# SC-1000527_SCH_IMUPlusMAGIslands_Page1.net
KiCad netlist of a schematic drawn in Altium Designer
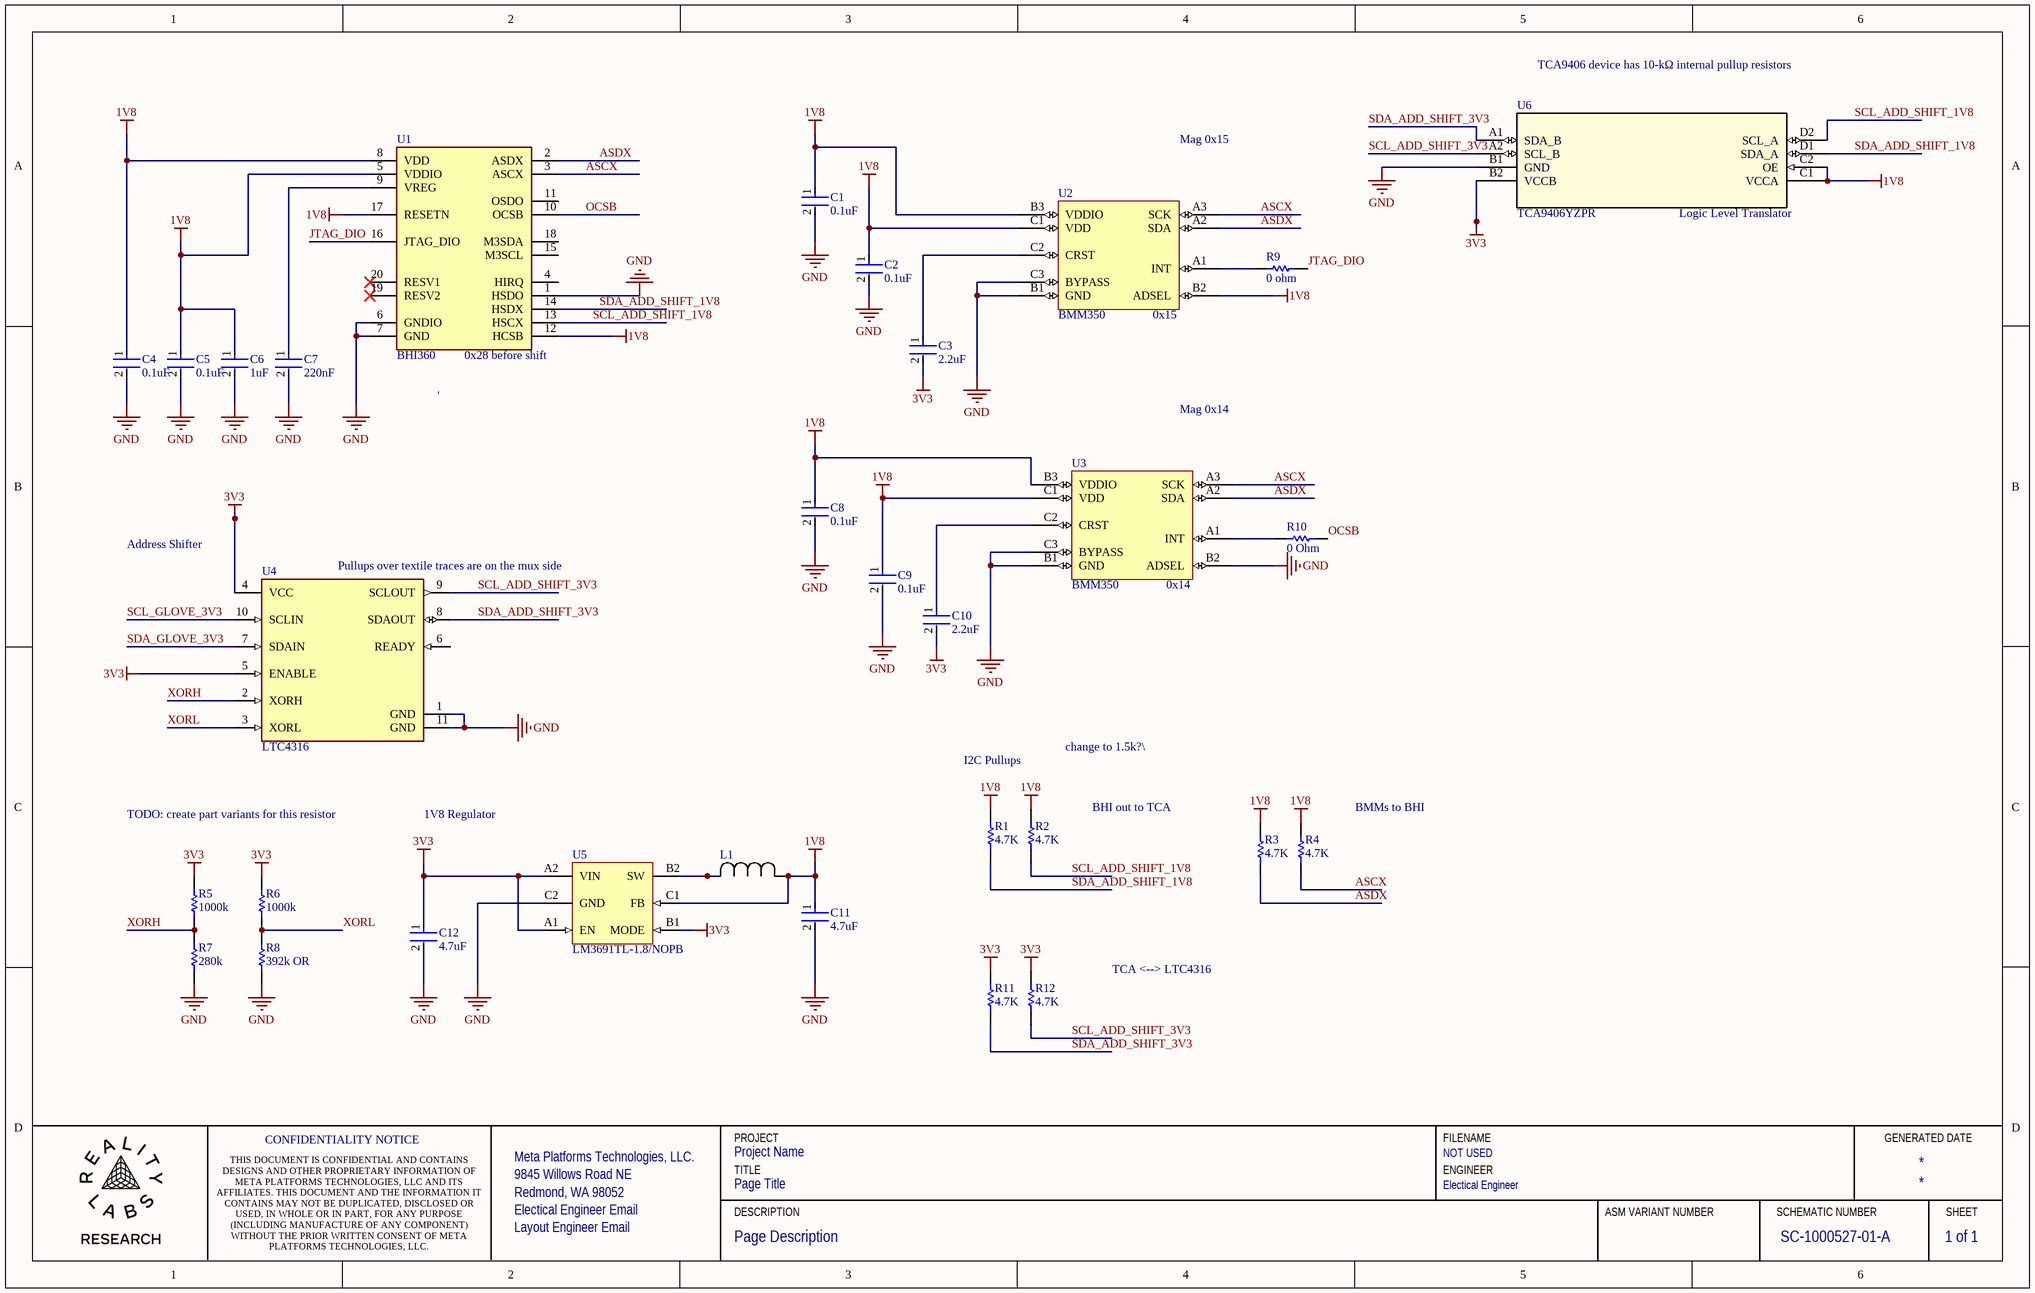
[diagram p0: SC-1000527_SCH_IMUPlusMAGIslands_Page1.SchDoc]

(export (version "E")
  (design (tool "Eeschema 10.0.6"))
  (components
    (comp (ref "C1")
      (value "0.1uF")
      (footprint "FP-GRM033-0_03-IPC_C")
      (description "Chip Multilayer Ceramic Capacitors for General Purpose, 0201, 0.10uF, X5R, 15%, 10%, 10V")
      (fields (field (name "TOLERANCE") "10%") (field (name "VOLTAGE") "10V"))
      (libsource (lib "Altium Content Vault") (part "b4654b650e69147ec39a6b967a45e02"))
    )
    (comp (ref "C2")
      (value "0.1uF")
      (footprint "FP-GRM033-0_03-IPC_C")
      (description "Chip Multilayer Ceramic Capacitors for General Purpose, 0201, 0.10uF, X5R, 15%, 10%, 10V")
      (fields (field (name "TOLERANCE") "10%") (field (name "VOLTAGE") "10V"))
      (libsource (lib "Altium Content Vault") (part "b4654b650e69147ec39a6b967a45e02"))
    )
    (comp (ref "C3")
      (value "2.2uF")
      (footprint "FP-GRM033-0_09-IPC_B")
      (description "Chip Multilayer Ceramic Capacitors for General Purpose, 0201, 2.2uF, X5R, 15%, 10%, 10V")
      (fields (field (name "TOLERANCE") "10%"))
      (libsource (lib "Altium Content Vault") (part "02cd4be3c70576c341d710602a673aa"))
    )
    (comp (ref "C4")
      (value "0.1uF")
      (footprint "FP-GRM033-0_03-IPC_C")
      (description "Chip Multilayer Ceramic Capacitors for General Purpose, 0201, 0.10uF, X5R, 15%, 10%, 10V")
      (fields (field (name "TOLERANCE") "10%") (field (name "VOLTAGE") "10V"))
      (libsource (lib "Altium Content Vault") (part "b4654b650e69147ec39a6b967a45e02"))
    )
    (comp (ref "C5")
      (value "0.1uF")
      (footprint "FP-GRM033-0_03-IPC_C")
      (description "Chip Multilayer Ceramic Capacitors for General Purpose, 0201, 0.10uF, X5R, 15%, 10%, 10V")
      (fields (field (name "TOLERANCE") "10%") (field (name "VOLTAGE") "10V"))
      (libsource (lib "Altium Content Vault") (part "b4654b650e69147ec39a6b967a45e02"))
    )
    (comp (ref "C6")
      (value "1uF")
      (footprint "FP-GRM033-0_05-e01_0_2-IPC_C")
      (description "Chip Multilayer Ceramic Capacitors for General Purpose, 0201, 1.0uF, X5R, 15%, 20%, 4V")
      (fields (field (name "TOLERANCE") "20%"))
      (libsource (lib "Altium Content Vault") (part "02cd4be3c70576c341d710602a673aa"))
    )
    (comp (ref "C7")
      (value "220nF")
      (footprint "FP-GRM033-0_03-MFG")
      (description "Chip Multilayer Ceramic Capacitors for General Purpose, 0201, 0.22uF, X6S, 22%, 10%, 6.3V")
      (fields (field (name "TOLERANCE") "10%"))
      (libsource (lib "Altium Content Vault") (part "b4654b650e69147ec39a6b967a45e02"))
    )
    (comp (ref "C8")
      (value "0.1uF")
      (footprint "FP-GRM033-0_03-IPC_C")
      (description "Chip Multilayer Ceramic Capacitors for General Purpose, 0201, 0.10uF, X5R, 15%, 10%, 10V")
      (fields (field (name "TOLERANCE") "10%") (field (name "VOLTAGE") "10V"))
      (libsource (lib "Altium Content Vault") (part "b4654b650e69147ec39a6b967a45e02"))
    )
    (comp (ref "C9")
      (value "0.1uF")
      (footprint "FP-GRM033-0_03-IPC_C")
      (description "Chip Multilayer Ceramic Capacitors for General Purpose, 0201, 0.10uF, X5R, 15%, 10%, 10V")
      (fields (field (name "TOLERANCE") "10%") (field (name "VOLTAGE") "10V"))
      (libsource (lib "Altium Content Vault") (part "b4654b650e69147ec39a6b967a45e02"))
    )
    (comp (ref "C10")
      (value "2.2uF")
      (footprint "FP-GRM033-0_09-IPC_B")
      (description "Chip Multilayer Ceramic Capacitors for General Purpose, 0201, 2.2uF, X5R, 15%, 10%, 10V")
      (fields (field (name "TOLERANCE") "10%"))
      (libsource (lib "Altium Content Vault") (part "02cd4be3c70576c341d710602a673aa"))
    )
    (comp (ref "C11")
      (value "4.7uF")
      (footprint "FP-CL828-IPC_C")
      (description "Cap Ceramic 4.7uF 10V X5R ±10% SMD 0402 +85°C Paper T/R")
      (fields (field (name "TOLERANCE") "10%"))
      (libsource (lib "Altium Content Vault") (part "b4654b650e69147ec39a6b967a45e02"))
    )
    (comp (ref "C12")
      (value "4.7uF")
      (footprint "FP-CL828-IPC_C")
      (description "Cap Ceramic 4.7uF 10V X5R ±10% SMD 0402 +85°C Paper T/R")
      (fields (field (name "TOLERANCE") "10%"))
      (libsource (lib "Altium Content Vault") (part "b4654b650e69147ec39a6b967a45e02"))
    )
    (comp (ref "L1")
      (value "MCHK1608T1R0MKN")
      (footprint "IND_MCHK1608T1R0MKN_TAY")
      (description "No Description Available")
      (fields (field (name "COPYRIGHT") "Copyright (C) 2024 Ultra Librarian. All rights reserved."))
      (libsource (lib "MCHK1608T1R0MKN") (part "MCHK1608T1R0MKN"))
    )
    (comp (ref "R1")
      (value "4.7K")
      (footprint "RESC0603X26X15NL03T05")
      (fields (field (name "PART NUMBER") "ERJ-1GEF4701C") (field (name "MANUFACTURER") "Panasonic"))
      (libsource (lib "Altium Content Vault") (part "RES"))
    )
    (comp (ref "R2")
      (value "4.7K")
      (footprint "RESC0603X26X15NL03T05")
      (fields (field (name "PART NUMBER") "ERJ-1GEF4701C") (field (name "MANUFACTURER") "Panasonic"))
      (libsource (lib "Altium Content Vault") (part "RES"))
    )
    (comp (ref "R3")
      (value "4.7K")
      (footprint "RESC0603X26X15NL03T05")
      (fields (field (name "PART NUMBER") "ERJ-1GEF4701C") (field (name "MANUFACTURER") "Panasonic"))
      (libsource (lib "Altium Content Vault") (part "RES"))
    )
    (comp (ref "R4")
      (value "4.7K")
      (footprint "RESC0603X26X15NL03T05")
      (fields (field (name "PART NUMBER") "ERJ-1GEF4701C") (field (name "MANUFACTURER") "Panasonic"))
      (libsource (lib "Altium Content Vault") (part "RES"))
    )
    (comp (ref "R5")
      (value "1000k")
      (footprint "RESC0603X26X15LL03T05")
      (fields (field (name "MANUFACTURER") "Panasonic") (field (name "PART NUMBER") "ERJ1GNF1004C"))
      (libsource (lib "Altium Content Vault") (part "RES"))
    )
    (comp (ref "R6")
      (value "1000k")
      (footprint "RESC0603X26X15LL03T05")
      (fields (field (name "MANUFACTURER") "Panasonic") (field (name "PART NUMBER") "ERJ1GNF1004C"))
      (libsource (lib "Altium Content Vault") (part "RES"))
    )
    (comp (ref "R7")
      (value "280k")
      (footprint "RESC0603X26X15LL03T05")
      (fields (field (name "MANUFACTURER") "Panasonic") (field (name "PART NUMBER") "ERJ-1GNF2803C"))
      (libsource (lib "Altium Content Vault") (part "RES"))
    )
    (comp (ref "R8")
      (value "392k OR")
      (footprint "RESC0603X26X15LL03T05")
      (fields (field (name "PART NUMBER") "ERJ-1GEF3923C") (field (name "MANUFACTURER") "Panasonic"))
      (libsource (lib "Altium Content Vault") (part "RES"))
    )
    (comp (ref "R9")
      (value "0 ohm")
      (footprint "RESC0603X28X15NL5T05")
      (description "Chip Resistor, 0 Ohm, Jumper, 0.05 W, -55 to 155 degC, 0201 (0603 Metric), RoHS, Tape and Reel")
      (fields (field (name "TOLERANCE") "5%"))
      (libsource (lib "Altium Content Vault") (part "RES-2"))
    )
    (comp (ref "R10")
      (value "0 Ohm")
      (footprint "RESC0603X28X15NL5T05")
      (description "Chip Resistor, 0 Ohm, Jumper, 0.05 W, -55 to 155 degC, 0201 (0603 Metric), RoHS, Tape and Reel")
      (fields (field (name "TOLERANCE") "5%"))
      (libsource (lib "Altium Content Vault") (part "RES-2"))
    )
    (comp (ref "R11")
      (value "4.7K")
      (footprint "RESC0603X26X15NL03T05")
      (fields (field (name "PART NUMBER") "ERJ-1GEF4701C") (field (name "MANUFACTURER") "Panasonic"))
      (libsource (lib "Altium Content Vault") (part "RES"))
    )
    (comp (ref "R12")
      (value "4.7K")
      (footprint "RESC0603X26X15NL03T05")
      (fields (field (name "PART NUMBER") "ERJ-1GEF4701C") (field (name "MANUFACTURER") "Panasonic"))
      (libsource (lib "Altium Content Vault") (part "RES"))
    )
    (comp (ref "U1")
      (value "BHI360")
      (footprint "BHI360")
      (fields (field (name "MOUSER PART NUMBER") "262-BHI360"))
      (libsource (lib "BHI360") (part "BHI360"))
    )
    (comp (ref "U2") (value "BMM350") (footprint "BMM350") (libsource (lib "bmm350") (part "BMM350")))
    (comp (ref "U3") (value "BMM350") (footprint "BMM350") (libsource (lib "bmm350") (part "BMM350")))
    (comp (ref "U4")
      (value "LTC4316")
      (footprint "FP-DD-10-05-08-1699-MFG")
      (description "LTC4316IDD#TRPBF Interface - Specialized 1x I2C/SMBus Address Translator")
      (libsource (lib "Altium Content Vault") (part "6e8e37fec79d27c4a0e56ed400e0b46"))
    )
    (comp (ref "U5")
      (value "LM3691TL-1.8/NOPB")
      (footprint "YZR0006APAF")
      (fields (field (name "MANUFACTURER") "Texas Instruments"))
      (libsource (lib "Altium Content Vault") (part "PM-DCDC-LM3691-6"))
    )
    (comp (ref "U6")
      (value "TCA9406YZPR")
      (footprint "YZP8")
      (description "No Description Available")
      (fields (field (name "COPYRIGHT") "Copyright (C) 2024 Ultra Librarian. All rights reserved."))
      (libsource (lib "TCA9406YZPR") (part "TCA9406YZPR"))
    )
  )
  (nets
    (net (code "1") (name "/ASCX") (class "Default")
      (node (ref "R4") (pin "1") (pinfunction "1_1") (pintype "passive"))
      (node (ref "U1") (pin "3") (pinfunction "ASCX_3") (pintype "passive"))
      (node (ref "U2") (pin "A3") (pinfunction "SCK_A3") (pintype "bidirectional"))
      (node (ref "U3") (pin "A3") (pinfunction "SCK_A3") (pintype "bidirectional"))
    )
    (net (code "2") (name "/ASDX") (class "Default")
      (node (ref "R3") (pin "1") (pinfunction "1_1") (pintype "passive"))
      (node (ref "U1") (pin "2") (pinfunction "ASDX_2") (pintype "passive"))
      (node (ref "U2") (pin "A2") (pinfunction "SDA_A2") (pintype "bidirectional"))
      (node (ref "U3") (pin "A2") (pinfunction "SDA_A2") (pintype "bidirectional"))
    )
    (net (code "3") (name "/JTAG_DIO") (class "Default")
      (node (ref "R9") (pin "2") (pinfunction "2_2") (pintype "passive"))
      (node (ref "U1") (pin "16") (pinfunction "JTAG_DIO_16") (pintype "passive"))
    )
    (net (code "4") (name "/OCSB") (class "Default")
      (node (ref "R10") (pin "2") (pinfunction "2_2") (pintype "passive"))
      (node (ref "U1") (pin "10") (pinfunction "OCSB_10") (pintype "passive"))
    )
    (net (code "5") (name "/SCL_ADD_SHIFT_1V8") (class "Default")
      (node (ref "R2") (pin "1") (pinfunction "1_1") (pintype "passive"))
      (node (ref "U1") (pin "13") (pinfunction "HSCX_13") (pintype "passive"))
      (node (ref "U6") (pin "D2") (pinfunction "SCL_A_D2") (pintype "bidirectional"))
    )
    (net (code "6") (name "/SCL_ADD_SHIFT_3V3") (class "Default")
      (node (ref "R12") (pin "1") (pinfunction "1_1") (pintype "passive"))
      (node (ref "U4") (pin "9") (pinfunction "SCLOUT_9") (pintype "output"))
      (node (ref "U6") (pin "A2") (pinfunction "SCL_B_A2") (pintype "bidirectional"))
    )
    (net (code "7") (name "/SCL_GLOVE_3V3") (class "Default")
      (node (ref "U4") (pin "10") (pinfunction "SCLIN_10") (pintype "input"))
    )
    (net (code "8") (name "/SDA_ADD_SHIFT_1V8") (class "Default")
      (node (ref "R1") (pin "1") (pinfunction "1_1") (pintype "passive"))
      (node (ref "U1") (pin "14") (pinfunction "HSDX_14") (pintype "passive"))
      (node (ref "U6") (pin "D1") (pinfunction "SDA_A_D1") (pintype "bidirectional"))
    )
    (net (code "9") (name "/SDA_ADD_SHIFT_3V3") (class "Default")
      (node (ref "R11") (pin "1") (pinfunction "1_1") (pintype "passive"))
      (node (ref "U4") (pin "8") (pinfunction "SDAOUT_8") (pintype "bidirectional"))
      (node (ref "U6") (pin "A1") (pinfunction "SDA_B_A1") (pintype "bidirectional"))
    )
    (net (code "10") (name "/SDA_GLOVE_3V3") (class "Default")
      (node (ref "U4") (pin "7") (pinfunction "SDAIN_7") (pintype "input"))
    )
    (net (code "11") (name "/XORH") (class "Default")
      (node (ref "R5") (pin "1") (pinfunction "1_1") (pintype "passive"))
      (node (ref "R7") (pin "2") (pinfunction "2_2") (pintype "passive"))
      (node (ref "U4") (pin "2") (pinfunction "XORH_2") (pintype "input"))
    )
    (net (code "12") (name "/XORL") (class "Default")
      (node (ref "R6") (pin "1") (pinfunction "1_1") (pintype "passive"))
      (node (ref "R8") (pin "2") (pinfunction "2_2") (pintype "passive"))
      (node (ref "U4") (pin "3") (pinfunction "XORL_3") (pintype "input"))
    )
    (net (code "13") (name "1V8") (class "Default")
      (node (ref "C1") (pin "1") (pinfunction "1_1") (pintype "passive"))
      (node (ref "C11") (pin "1") (pinfunction "1_1") (pintype "passive"))
      (node (ref "C2") (pin "1") (pinfunction "1_1") (pintype "passive"))
      (node (ref "C4") (pin "1") (pinfunction "1_1") (pintype "passive"))
      (node (ref "C5") (pin "1") (pinfunction "1_1") (pintype "passive"))
      (node (ref "C6") (pin "1") (pinfunction "1_1") (pintype "passive"))
      (node (ref "C8") (pin "1") (pinfunction "1_1") (pintype "passive"))
      (node (ref "C9") (pin "1") (pinfunction "1_1") (pintype "passive"))
      (node (ref "L1") (pin "1") (pinfunction "1_1") (pintype "passive"))
      (node (ref "R1") (pin "2") (pinfunction "2_2") (pintype "passive"))
      (node (ref "R2") (pin "2") (pinfunction "2_2") (pintype "passive"))
      (node (ref "R3") (pin "2") (pinfunction "2_2") (pintype "passive"))
      (node (ref "R4") (pin "2") (pinfunction "2_2") (pintype "passive"))
      (node (ref "U1") (pin "12") (pinfunction "HCSB_12") (pintype "passive"))
      (node (ref "U1") (pin "17") (pinfunction "RESETN_17") (pintype "passive"))
      (node (ref "U1") (pin "5") (pinfunction "VDDIO_5") (pintype "passive"))
      (node (ref "U1") (pin "8") (pinfunction "VDD_8") (pintype "passive"))
      (node (ref "U2") (pin "B2") (pinfunction "ADSEL_B2") (pintype "bidirectional"))
      (node (ref "U2") (pin "B3") (pinfunction "VDDIO_B3") (pintype "bidirectional"))
      (node (ref "U2") (pin "C1") (pinfunction "VDD_C1") (pintype "bidirectional"))
      (node (ref "U3") (pin "B3") (pinfunction "VDDIO_B3") (pintype "bidirectional"))
      (node (ref "U3") (pin "C1") (pinfunction "VDD_C1") (pintype "bidirectional"))
      (node (ref "U5") (pin "C1") (pinfunction "FB_C1") (pintype "input"))
      (node (ref "U6") (pin "C1") (pinfunction "VCCA_C1") (pintype "power_in"))
      (node (ref "U6") (pin "C2") (pinfunction "OE_C2") (pintype "input"))
    )
    (net (code "14") (name "3V3") (class "Default")
      (node (ref "C10") (pin "2") (pinfunction "2_2") (pintype "passive"))
      (node (ref "C12") (pin "1") (pinfunction "1_1") (pintype "passive"))
      (node (ref "C3") (pin "2") (pinfunction "2_2") (pintype "passive"))
      (node (ref "R11") (pin "2") (pinfunction "2_2") (pintype "passive"))
      (node (ref "R12") (pin "2") (pinfunction "2_2") (pintype "passive"))
      (node (ref "R5") (pin "2") (pinfunction "2_2") (pintype "passive"))
      (node (ref "R6") (pin "2") (pinfunction "2_2") (pintype "passive"))
      (node (ref "U4") (pin "4") (pinfunction "VCC_4") (pintype "power_in"))
      (node (ref "U4") (pin "5") (pinfunction "ENABLE_5") (pintype "input"))
      (node (ref "U5") (pin "A1") (pinfunction "EN_A1") (pintype "input"))
      (node (ref "U5") (pin "A2") (pinfunction "VIN_A2") (pintype "power_in"))
      (node (ref "U5") (pin "B1") (pinfunction "MODE_B1") (pintype "input"))
      (node (ref "U6") (pin "B2") (pinfunction "VCCB_B2") (pintype "power_in"))
    )
    (net (code "15") (name "GND") (class "Default")
      (node (ref "C1") (pin "2") (pinfunction "2_2") (pintype "passive"))
      (node (ref "C11") (pin "2") (pinfunction "2_2") (pintype "passive"))
      (node (ref "C12") (pin "2") (pinfunction "2_2") (pintype "passive"))
      (node (ref "C2") (pin "2") (pinfunction "2_2") (pintype "passive"))
      (node (ref "C4") (pin "2") (pinfunction "2_2") (pintype "passive"))
      (node (ref "C5") (pin "2") (pinfunction "2_2") (pintype "passive"))
      (node (ref "C6") (pin "2") (pinfunction "2_2") (pintype "passive"))
      (node (ref "C7") (pin "2") (pinfunction "2_2") (pintype "passive"))
      (node (ref "C8") (pin "2") (pinfunction "2_2") (pintype "passive"))
      (node (ref "C9") (pin "2") (pinfunction "2_2") (pintype "passive"))
      (node (ref "R7") (pin "1") (pinfunction "1_1") (pintype "passive"))
      (node (ref "R8") (pin "1") (pinfunction "1_1") (pintype "passive"))
      (node (ref "U1") (pin "1") (pinfunction "HSDO_1") (pintype "passive"))
      (node (ref "U1") (pin "6") (pinfunction "GNDIO_6") (pintype "passive"))
      (node (ref "U1") (pin "7") (pinfunction "GND_7") (pintype "passive"))
      (node (ref "U2") (pin "B1") (pinfunction "GND_B1") (pintype "bidirectional"))
      (node (ref "U2") (pin "C3") (pinfunction "BYPASS_C3") (pintype "bidirectional"))
      (node (ref "U3") (pin "B1") (pinfunction "GND_B1") (pintype "bidirectional"))
      (node (ref "U3") (pin "B2") (pinfunction "ADSEL_B2") (pintype "bidirectional"))
      (node (ref "U3") (pin "C3") (pinfunction "BYPASS_C3") (pintype "bidirectional"))
      (node (ref "U4") (pin "1") (pinfunction "GND_1") (pintype "power_in"))
      (node (ref "U4") (pin "11") (pinfunction "GND_11") (pintype "power_in"))
      (node (ref "U5") (pin "C2") (pinfunction "GND_C2") (pintype "power_in"))
      (node (ref "U6") (pin "B1") (pinfunction "GND_B1") (pintype "power_in"))
    )
    (net (code "16") (name "Net-(U1-VREG)") (class "Default")
      (node (ref "C7") (pin "1") (pinfunction "1_1") (pintype "passive"))
      (node (ref "U1") (pin "9") (pinfunction "VREG_9") (pintype "passive"))
    )
    (net (code "17") (name "Net-(U2-CRST)") (class "Default")
      (node (ref "C3") (pin "1") (pinfunction "1_1") (pintype "passive"))
      (node (ref "U2") (pin "C2") (pinfunction "CRST_C2") (pintype "bidirectional"))
    )
    (net (code "18") (name "Net-(U2-INT)") (class "Default")
      (node (ref "R9") (pin "1") (pinfunction "1_1") (pintype "passive"))
      (node (ref "U2") (pin "A1") (pinfunction "INT_A1") (pintype "bidirectional"))
    )
    (net (code "19") (name "Net-(U3-CRST)") (class "Default")
      (node (ref "C10") (pin "1") (pinfunction "1_1") (pintype "passive"))
      (node (ref "U3") (pin "C2") (pinfunction "CRST_C2") (pintype "bidirectional"))
    )
    (net (code "20") (name "Net-(U3-INT)") (class "Default")
      (node (ref "R10") (pin "1") (pinfunction "1_1") (pintype "passive"))
      (node (ref "U3") (pin "A1") (pinfunction "INT_A1") (pintype "bidirectional"))
    )
    (net (code "21") (name "Net-(U5-SW)") (class "Default")
      (node (ref "L1") (pin "2") (pinfunction "2_2") (pintype "passive"))
      (node (ref "U5") (pin "B2") (pinfunction "SW_B2") (pintype "power_in"))
    )
    (net (code "22") (name "unconnected-(U1-HIRQ-Pad4)") (class "Default")
      (node (ref "U1") (pin "4") (pinfunction "HIRQ_4") (pintype "passive"))
    )
    (net (code "23") (name "unconnected-(U1-M3SCL-Pad15)") (class "Default")
      (node (ref "U1") (pin "15") (pinfunction "M3SCL_15") (pintype "passive"))
    )
    (net (code "24") (name "unconnected-(U1-M3SDA-Pad18)") (class "Default")
      (node (ref "U1") (pin "18") (pinfunction "M3SDA_18") (pintype "passive"))
    )
    (net (code "25") (name "unconnected-(U1-OSDO-Pad11)") (class "Default")
      (node (ref "U1") (pin "11") (pinfunction "OSDO_11") (pintype "passive"))
    )
    (net (code "26") (name "unconnected-(U1-RESV1-Pad20)") (class "Default")
      (node (ref "U1") (pin "20") (pinfunction "RESV1_20") (pintype "passive+no_connect"))
    )
    (net (code "27") (name "unconnected-(U1-RESV2-Pad19)") (class "Default")
      (node (ref "U1") (pin "19") (pinfunction "RESV2_19") (pintype "passive+no_connect"))
    )
    (net (code "28") (name "unconnected-(U4-READY-Pad6)") (class "Default")
      (node (ref "U4") (pin "6") (pinfunction "READY_6") (pintype "input"))
    )
  )
)
